# Entrada_comestero_rm5.net
KiCad netlist of a schematic drawn in Altium Designer
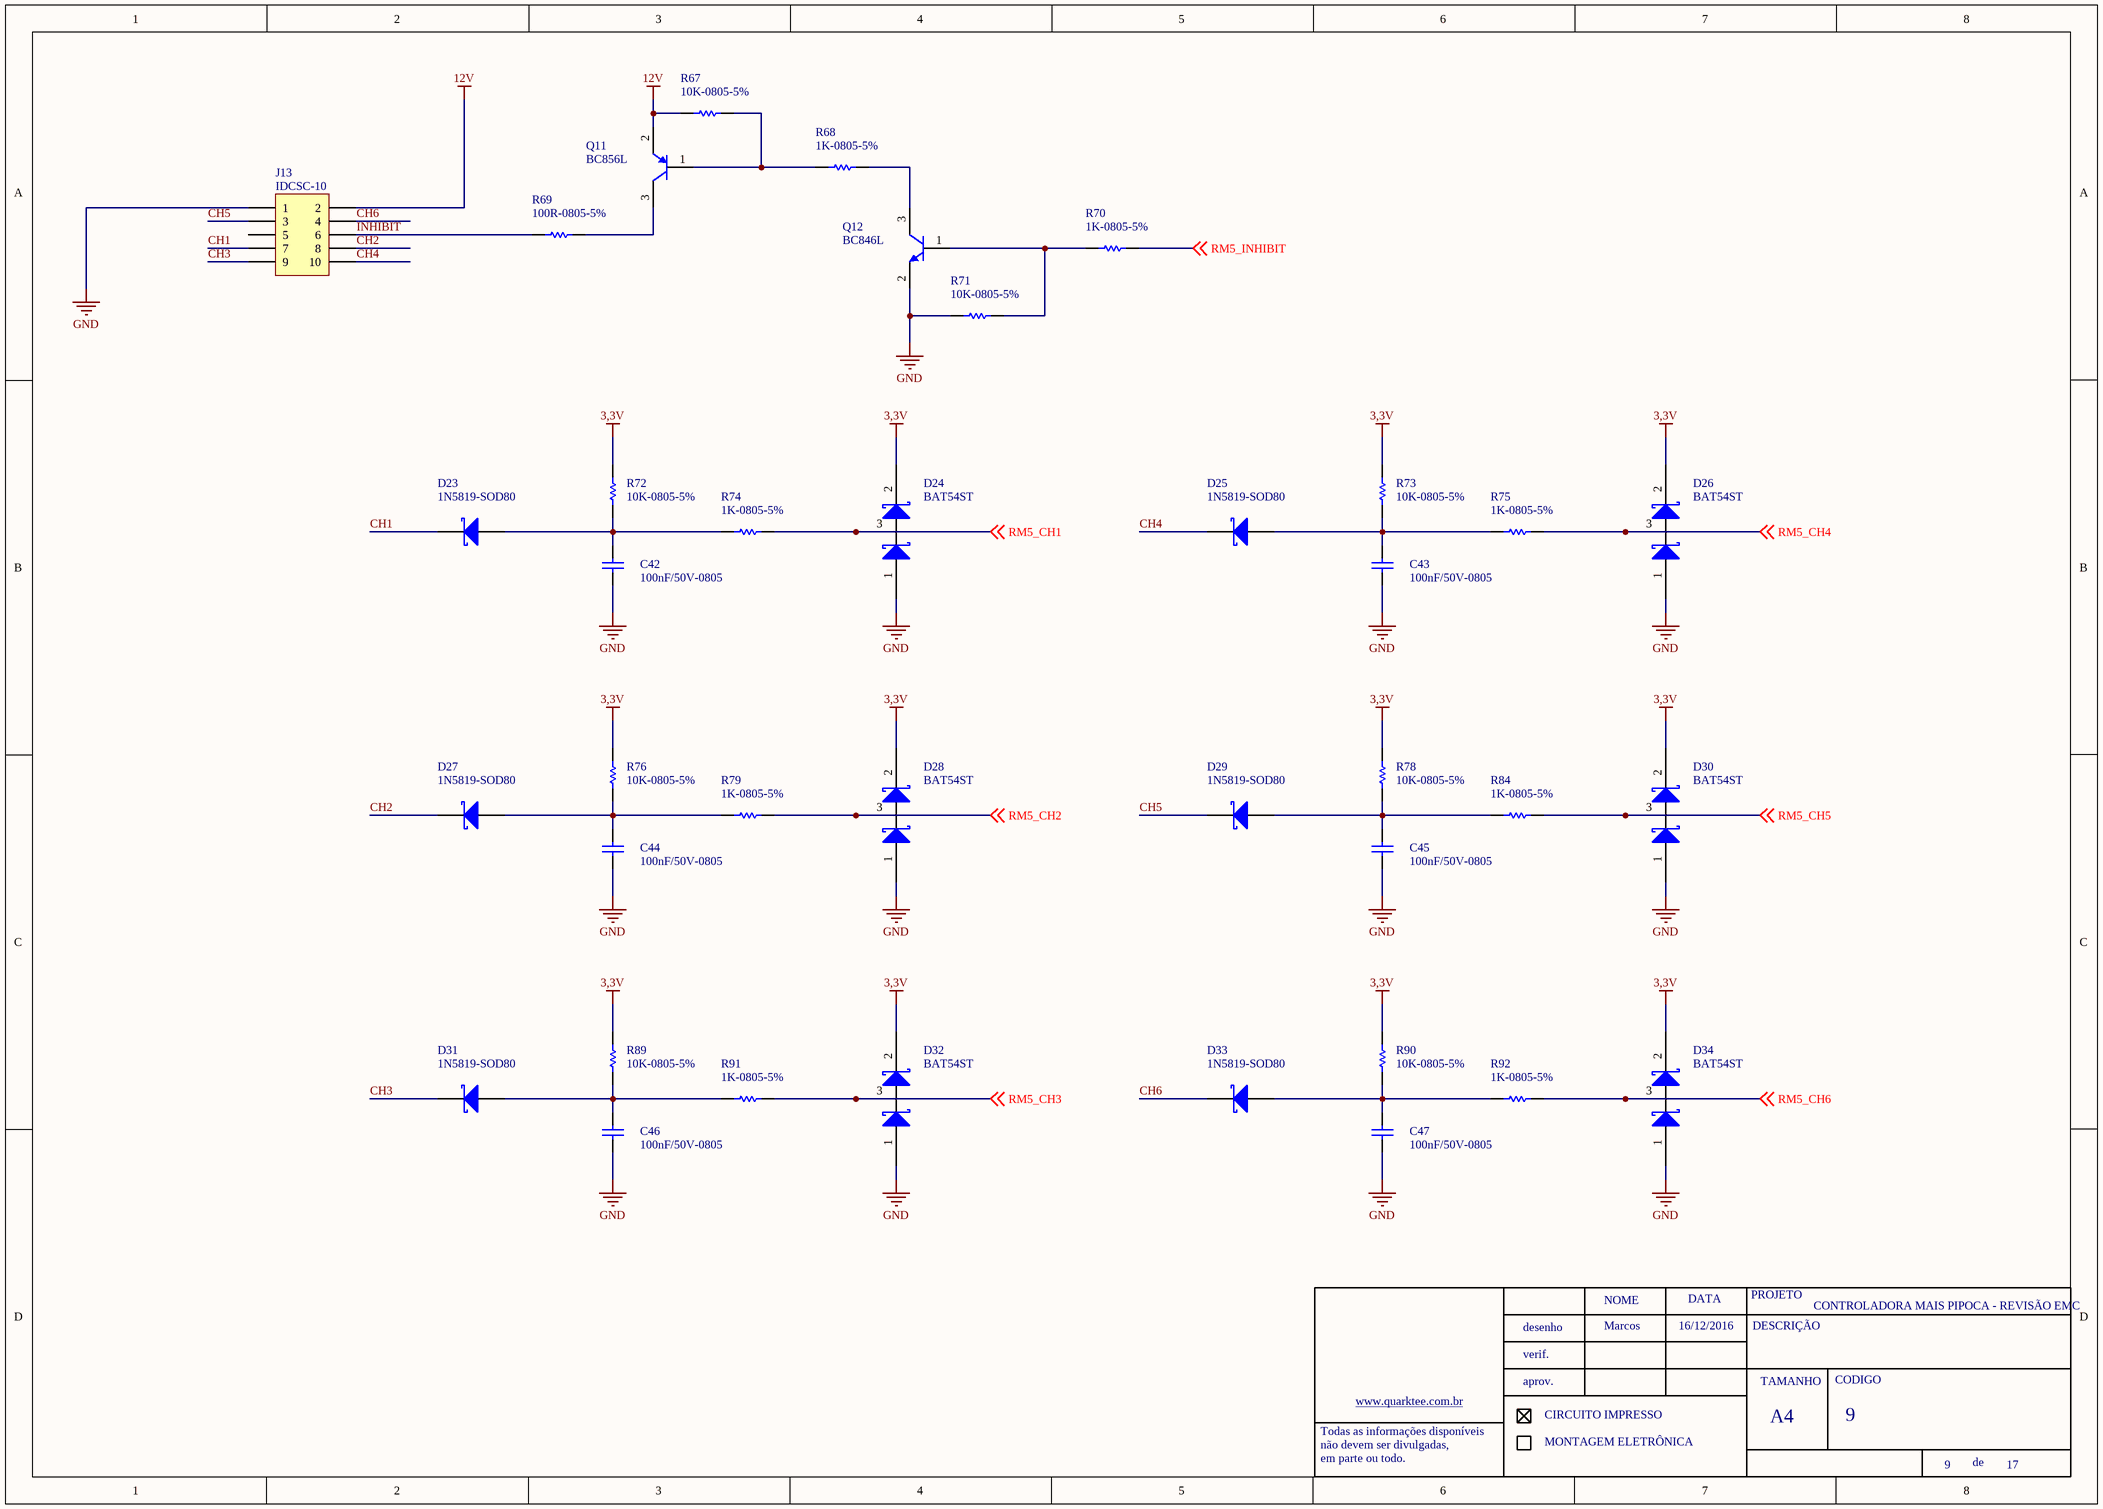
[diagram p0: Entrada_comestero_rm5.SchDoc]

(export (version "E")
  (design (tool "Eeschema 10.0.6"))
  (components
    (comp (ref "C42")
      (value "100nF/50V-0805")
      (footprint "0805-REVISADO ONDA")
      (libsource (lib "AquinoLib") (part "100nF/50-0805-NPO"))
    )
    (comp (ref "C43")
      (value "100nF/50V-0805")
      (footprint "0805-REVISADO ONDA")
      (libsource (lib "AquinoLib") (part "100nF/50-0805-NPO"))
    )
    (comp (ref "C44")
      (value "100nF/50V-0805")
      (footprint "0805-REVISADO ONDA")
      (libsource (lib "AquinoLib") (part "100nF/50-0805-NPO"))
    )
    (comp (ref "C45")
      (value "100nF/50V-0805")
      (footprint "0805-REVISADO ONDA")
      (libsource (lib "AquinoLib") (part "100nF/50-0805-NPO"))
    )
    (comp (ref "C46")
      (value "100nF/50V-0805")
      (footprint "0805-REVISADO ONDA")
      (libsource (lib "AquinoLib") (part "100nF/50-0805-NPO"))
    )
    (comp (ref "C47")
      (value "100nF/50V-0805")
      (footprint "0805-REVISADO ONDA")
      (libsource (lib "AquinoLib") (part "100nF/50-0805-NPO"))
    )
    (comp (ref "D23")
      (value "1N5819-SOD80")
      (footprint "MINIMLEF/SOD80 - REVISADO ONDA")
      (libsource (lib "AquinoLib") (part "1N5819-SOD80"))
    )
    (comp (ref "D24")
      (value "BAT54ST")
      (footprint "SOT23 - REVISADO ONDA")
      (libsource (lib "AquinoLib") (part "BAT54ST"))
    )
    (comp (ref "D25")
      (value "1N5819-SOD80")
      (footprint "MINIMLEF/SOD80 - REVISADO ONDA")
      (libsource (lib "AquinoLib") (part "1N5819-SOD80"))
    )
    (comp (ref "D26")
      (value "BAT54ST")
      (footprint "SOT23 - REVISADO ONDA")
      (libsource (lib "AquinoLib") (part "BAT54ST"))
    )
    (comp (ref "D27")
      (value "1N5819-SOD80")
      (footprint "MINIMLEF/SOD80 - REVISADO ONDA")
      (libsource (lib "AquinoLib") (part "1N5819-SOD80"))
    )
    (comp (ref "D28")
      (value "BAT54ST")
      (footprint "SOT23 - REVISADO ONDA")
      (libsource (lib "AquinoLib") (part "BAT54ST"))
    )
    (comp (ref "D29")
      (value "1N5819-SOD80")
      (footprint "MINIMLEF/SOD80 - REVISADO ONDA")
      (libsource (lib "AquinoLib") (part "1N5819-SOD80"))
    )
    (comp (ref "D30")
      (value "BAT54ST")
      (footprint "SOT23 - REVISADO ONDA")
      (libsource (lib "AquinoLib") (part "BAT54ST"))
    )
    (comp (ref "D31")
      (value "1N5819-SOD80")
      (footprint "MINIMLEF/SOD80 - REVISADO ONDA")
      (libsource (lib "AquinoLib") (part "1N5819-SOD80"))
    )
    (comp (ref "D32")
      (value "BAT54ST")
      (footprint "SOT23 - REVISADO ONDA")
      (libsource (lib "AquinoLib") (part "BAT54ST"))
    )
    (comp (ref "D33")
      (value "1N5819-SOD80")
      (footprint "MINIMLEF/SOD80 - REVISADO ONDA")
      (libsource (lib "AquinoLib") (part "1N5819-SOD80"))
    )
    (comp (ref "D34")
      (value "BAT54ST")
      (footprint "SOT23 - REVISADO ONDA")
      (libsource (lib "AquinoLib") (part "BAT54ST"))
    )
    (comp (ref "J13")
      (value "IDCSC-10")
      (footprint "IDCSC-10")
      (description "CONECTOR HEADER 10 VIAS 90º")
      (libsource (lib "ChaveDigital3") (part "IDCSN"))
    )
    (comp (ref "Q11")
      (value "BC856L")
      (footprint "SOT23 - REVISADO ONDA")
      (libsource (lib "AquinoLib") (part "BC856L"))
    )
    (comp (ref "Q12")
      (value "BC846L")
      (footprint "SOT23 - REVISADO ONDA")
      (libsource (lib "AquinoLib") (part "BC846"))
    )
    (comp (ref "R67")
      (value "10K-0805-5%")
      (footprint "0805-REVISADO ONDA")
      (libsource (lib "AquinoLib") (part "10K-0805-5%"))
    )
    (comp (ref "R68")
      (value "1K-0805-5%")
      (footprint "0805-REVISADO ONDA")
      (libsource (lib "AquinoLib") (part "1K-0805-5%"))
    )
    (comp (ref "R69")
      (value "100R-0805-5%")
      (footprint "0805-REVISADO ONDA")
      (libsource (lib "AquinoLib") (part "100R-0805-5%"))
    )
    (comp (ref "R70")
      (value "1K-0805-5%")
      (footprint "0805-REVISADO ONDA")
      (description "100R-0805-5%")
      (libsource (lib "AquinoLib") (part "100R-0805-5%"))
    )
    (comp (ref "R71")
      (value "10K-0805-5%")
      (footprint "0805-REVISADO ONDA")
      (libsource (lib "AquinoLib") (part "10K-0805-5%"))
    )
    (comp (ref "R72")
      (value "10K-0805-5%")
      (footprint "0805-REVISADO ONDA")
      (libsource (lib "AquinoLib") (part "10K-0805-5%"))
    )
    (comp (ref "R73")
      (value "10K-0805-5%")
      (footprint "0805-REVISADO ONDA")
      (libsource (lib "AquinoLib") (part "10K-0805-5%"))
    )
    (comp (ref "R74")
      (value "1K-0805-5%")
      (footprint "0805-REVISADO ONDA")
      (libsource (lib "AquinoLib") (part "1K-0805-5%"))
    )
    (comp (ref "R75")
      (value "1K-0805-5%")
      (footprint "0805-REVISADO ONDA")
      (libsource (lib "AquinoLib") (part "1K-0805-5%"))
    )
    (comp (ref "R76")
      (value "10K-0805-5%")
      (footprint "0805-REVISADO ONDA")
      (libsource (lib "AquinoLib") (part "10K-0805-5%"))
    )
    (comp (ref "R78")
      (value "10K-0805-5%")
      (footprint "0805-REVISADO ONDA")
      (libsource (lib "AquinoLib") (part "10K-0805-5%"))
    )
    (comp (ref "R79")
      (value "1K-0805-5%")
      (footprint "0805-REVISADO ONDA")
      (libsource (lib "AquinoLib") (part "1K-0805-5%"))
    )
    (comp (ref "R84")
      (value "1K-0805-5%")
      (footprint "0805-REVISADO ONDA")
      (libsource (lib "AquinoLib") (part "1K-0805-5%"))
    )
    (comp (ref "R89")
      (value "10K-0805-5%")
      (footprint "0805-REVISADO ONDA")
      (libsource (lib "AquinoLib") (part "10K-0805-5%"))
    )
    (comp (ref "R90")
      (value "10K-0805-5%")
      (footprint "0805-REVISADO ONDA")
      (libsource (lib "AquinoLib") (part "10K-0805-5%"))
    )
    (comp (ref "R91")
      (value "1K-0805-5%")
      (footprint "0805-REVISADO ONDA")
      (libsource (lib "AquinoLib") (part "1K-0805-5%"))
    )
    (comp (ref "R92")
      (value "1K-0805-5%")
      (footprint "0805-REVISADO ONDA")
      (libsource (lib "AquinoLib") (part "1K-0805-5%"))
    )
  )
  (nets
    (net (code "1") (name "/CH1") (class "Default")
      (node (ref "D23") (pin "2") (pinfunction "K_2") (pintype "passive"))
      (node (ref "J13") (pin "7") (pinfunction "7_7") (pintype "passive"))
    )
    (net (code "2") (name "/CH2") (class "Default")
      (node (ref "D27") (pin "2") (pinfunction "K_2") (pintype "passive"))
      (node (ref "J13") (pin "8") (pinfunction "8_8") (pintype "passive"))
    )
    (net (code "3") (name "/CH3") (class "Default")
      (node (ref "D31") (pin "2") (pinfunction "K_2") (pintype "passive"))
      (node (ref "J13") (pin "9") (pinfunction "9_9") (pintype "passive"))
    )
    (net (code "4") (name "/CH4") (class "Default")
      (node (ref "D25") (pin "2") (pinfunction "K_2") (pintype "passive"))
      (node (ref "J13") (pin "10") (pinfunction "10_10") (pintype "passive"))
    )
    (net (code "5") (name "/CH5") (class "Default")
      (node (ref "D29") (pin "2") (pinfunction "K_2") (pintype "passive"))
      (node (ref "J13") (pin "3") (pinfunction "3_3") (pintype "passive"))
    )
    (net (code "6") (name "/CH6") (class "Default")
      (node (ref "D33") (pin "2") (pinfunction "K_2") (pintype "passive"))
      (node (ref "J13") (pin "4") (pinfunction "4_4") (pintype "passive"))
    )
    (net (code "7") (name "/INHIBIT") (class "Default")
      (node (ref "J13") (pin "6") (pinfunction "6_6") (pintype "passive"))
      (node (ref "R69") (pin "1") (pinfunction "1_1") (pintype "passive"))
    )
    (net (code "8") (name "3,3V") (class "Default")
      (node (ref "D24") (pin "2") (pinfunction "2_2") (pintype "passive"))
      (node (ref "D26") (pin "2") (pinfunction "2_2") (pintype "passive"))
      (node (ref "D28") (pin "2") (pinfunction "2_2") (pintype "passive"))
      (node (ref "D30") (pin "2") (pinfunction "2_2") (pintype "passive"))
      (node (ref "D32") (pin "2") (pinfunction "2_2") (pintype "passive"))
      (node (ref "D34") (pin "2") (pinfunction "2_2") (pintype "passive"))
      (node (ref "R72") (pin "2") (pinfunction "2_2") (pintype "passive"))
      (node (ref "R73") (pin "2") (pinfunction "2_2") (pintype "passive"))
      (node (ref "R76") (pin "2") (pinfunction "2_2") (pintype "passive"))
      (node (ref "R78") (pin "2") (pinfunction "2_2") (pintype "passive"))
      (node (ref "R89") (pin "2") (pinfunction "2_2") (pintype "passive"))
      (node (ref "R90") (pin "2") (pinfunction "2_2") (pintype "passive"))
    )
    (net (code "9") (name "12V") (class "Default")
      (node (ref "J13") (pin "2") (pinfunction "2_2") (pintype "passive"))
      (node (ref "Q11") (pin "2") (pinfunction "E_2") (pintype "passive"))
      (node (ref "R67") (pin "1") (pinfunction "1_1") (pintype "passive"))
    )
    (net (code "10") (name "GND") (class "Default")
      (node (ref "C42") (pin "1") (pinfunction "1_1") (pintype "passive"))
      (node (ref "C43") (pin "1") (pinfunction "1_1") (pintype "passive"))
      (node (ref "C44") (pin "1") (pinfunction "1_1") (pintype "passive"))
      (node (ref "C45") (pin "1") (pinfunction "1_1") (pintype "passive"))
      (node (ref "C46") (pin "1") (pinfunction "1_1") (pintype "passive"))
      (node (ref "C47") (pin "1") (pinfunction "1_1") (pintype "passive"))
      (node (ref "D24") (pin "1") (pinfunction "1_1") (pintype "passive"))
      (node (ref "D26") (pin "1") (pinfunction "1_1") (pintype "passive"))
      (node (ref "D28") (pin "1") (pinfunction "1_1") (pintype "passive"))
      (node (ref "D30") (pin "1") (pinfunction "1_1") (pintype "passive"))
      (node (ref "D32") (pin "1") (pinfunction "1_1") (pintype "passive"))
      (node (ref "D34") (pin "1") (pinfunction "1_1") (pintype "passive"))
      (node (ref "J13") (pin "1") (pinfunction "1_1") (pintype "passive"))
      (node (ref "Q12") (pin "2") (pinfunction "E_2") (pintype "passive"))
      (node (ref "R71") (pin "1") (pinfunction "1_1") (pintype "passive"))
    )
    (net (code "11") (name "Net-(D23-A)") (class "Default")
      (node (ref "C42") (pin "2") (pinfunction "2_2") (pintype "passive"))
      (node (ref "D23") (pin "1") (pinfunction "A_1") (pintype "passive"))
      (node (ref "R72") (pin "1") (pinfunction "1_1") (pintype "passive"))
      (node (ref "R74") (pin "1") (pinfunction "1_1") (pintype "passive"))
    )
    (net (code "12") (name "Net-(D25-A)") (class "Default")
      (node (ref "C43") (pin "2") (pinfunction "2_2") (pintype "passive"))
      (node (ref "D25") (pin "1") (pinfunction "A_1") (pintype "passive"))
      (node (ref "R73") (pin "1") (pinfunction "1_1") (pintype "passive"))
      (node (ref "R75") (pin "1") (pinfunction "1_1") (pintype "passive"))
    )
    (net (code "13") (name "Net-(D27-A)") (class "Default")
      (node (ref "C44") (pin "2") (pinfunction "2_2") (pintype "passive"))
      (node (ref "D27") (pin "1") (pinfunction "A_1") (pintype "passive"))
      (node (ref "R76") (pin "1") (pinfunction "1_1") (pintype "passive"))
      (node (ref "R79") (pin "1") (pinfunction "1_1") (pintype "passive"))
    )
    (net (code "14") (name "Net-(D29-A)") (class "Default")
      (node (ref "C45") (pin "2") (pinfunction "2_2") (pintype "passive"))
      (node (ref "D29") (pin "1") (pinfunction "A_1") (pintype "passive"))
      (node (ref "R78") (pin "1") (pinfunction "1_1") (pintype "passive"))
      (node (ref "R84") (pin "1") (pinfunction "1_1") (pintype "passive"))
    )
    (net (code "15") (name "Net-(D31-A)") (class "Default")
      (node (ref "C46") (pin "2") (pinfunction "2_2") (pintype "passive"))
      (node (ref "D31") (pin "1") (pinfunction "A_1") (pintype "passive"))
      (node (ref "R89") (pin "1") (pinfunction "1_1") (pintype "passive"))
      (node (ref "R91") (pin "1") (pinfunction "1_1") (pintype "passive"))
    )
    (net (code "16") (name "Net-(D33-A)") (class "Default")
      (node (ref "C47") (pin "2") (pinfunction "2_2") (pintype "passive"))
      (node (ref "D33") (pin "1") (pinfunction "A_1") (pintype "passive"))
      (node (ref "R90") (pin "1") (pinfunction "1_1") (pintype "passive"))
      (node (ref "R92") (pin "1") (pinfunction "1_1") (pintype "passive"))
    )
    (net (code "17") (name "Net-(Q11-B)") (class "Default")
      (node (ref "Q11") (pin "1") (pinfunction "B_1") (pintype "passive"))
      (node (ref "R67") (pin "2") (pinfunction "2_2") (pintype "passive"))
      (node (ref "R68") (pin "1") (pinfunction "1_1") (pintype "passive"))
    )
    (net (code "18") (name "Net-(Q11-C)") (class "Default")
      (node (ref "Q11") (pin "3") (pinfunction "C_3") (pintype "passive"))
      (node (ref "R69") (pin "2") (pinfunction "2_2") (pintype "passive"))
    )
    (net (code "19") (name "Net-(Q12-B)") (class "Default")
      (node (ref "Q12") (pin "1") (pinfunction "B_1") (pintype "passive"))
      (node (ref "R70") (pin "1") (pinfunction "1_1") (pintype "passive"))
      (node (ref "R71") (pin "2") (pinfunction "2_2") (pintype "passive"))
    )
    (net (code "20") (name "Net-(Q12-C)") (class "Default")
      (node (ref "Q12") (pin "3") (pinfunction "C_3") (pintype "passive"))
      (node (ref "R68") (pin "2") (pinfunction "2_2") (pintype "passive"))
    )
    (net (code "21") (name "RM5_CH1") (class "Default")
      (node (ref "D24") (pin "3") (pinfunction "3_3") (pintype "passive"))
      (node (ref "R74") (pin "2") (pinfunction "2_2") (pintype "passive"))
    )
    (net (code "22") (name "RM5_CH2") (class "Default")
      (node (ref "D28") (pin "3") (pinfunction "3_3") (pintype "passive"))
      (node (ref "R79") (pin "2") (pinfunction "2_2") (pintype "passive"))
    )
    (net (code "23") (name "RM5_CH3") (class "Default")
      (node (ref "D32") (pin "3") (pinfunction "3_3") (pintype "passive"))
      (node (ref "R91") (pin "2") (pinfunction "2_2") (pintype "passive"))
    )
    (net (code "24") (name "RM5_CH4") (class "Default")
      (node (ref "D26") (pin "3") (pinfunction "3_3") (pintype "passive"))
      (node (ref "R75") (pin "2") (pinfunction "2_2") (pintype "passive"))
    )
    (net (code "25") (name "RM5_CH5") (class "Default")
      (node (ref "D30") (pin "3") (pinfunction "3_3") (pintype "passive"))
      (node (ref "R84") (pin "2") (pinfunction "2_2") (pintype "passive"))
    )
    (net (code "26") (name "RM5_CH6") (class "Default")
      (node (ref "D34") (pin "3") (pinfunction "3_3") (pintype "passive"))
      (node (ref "R92") (pin "2") (pinfunction "2_2") (pintype "passive"))
    )
    (net (code "27") (name "RM5_INHIBIT") (class "Default")
      (node (ref "R70") (pin "2") (pinfunction "2_2") (pintype "passive"))
    )
    (net (code "28") (name "unconnected-(J13-Pad5)") (class "Default")
      (node (ref "J13") (pin "5") (pinfunction "5_5") (pintype "passive"))
    )
  )
)
